# Fri3D_2020_GameOn_01.net
KiCad netlist of a schematic drawn in Altium Designer
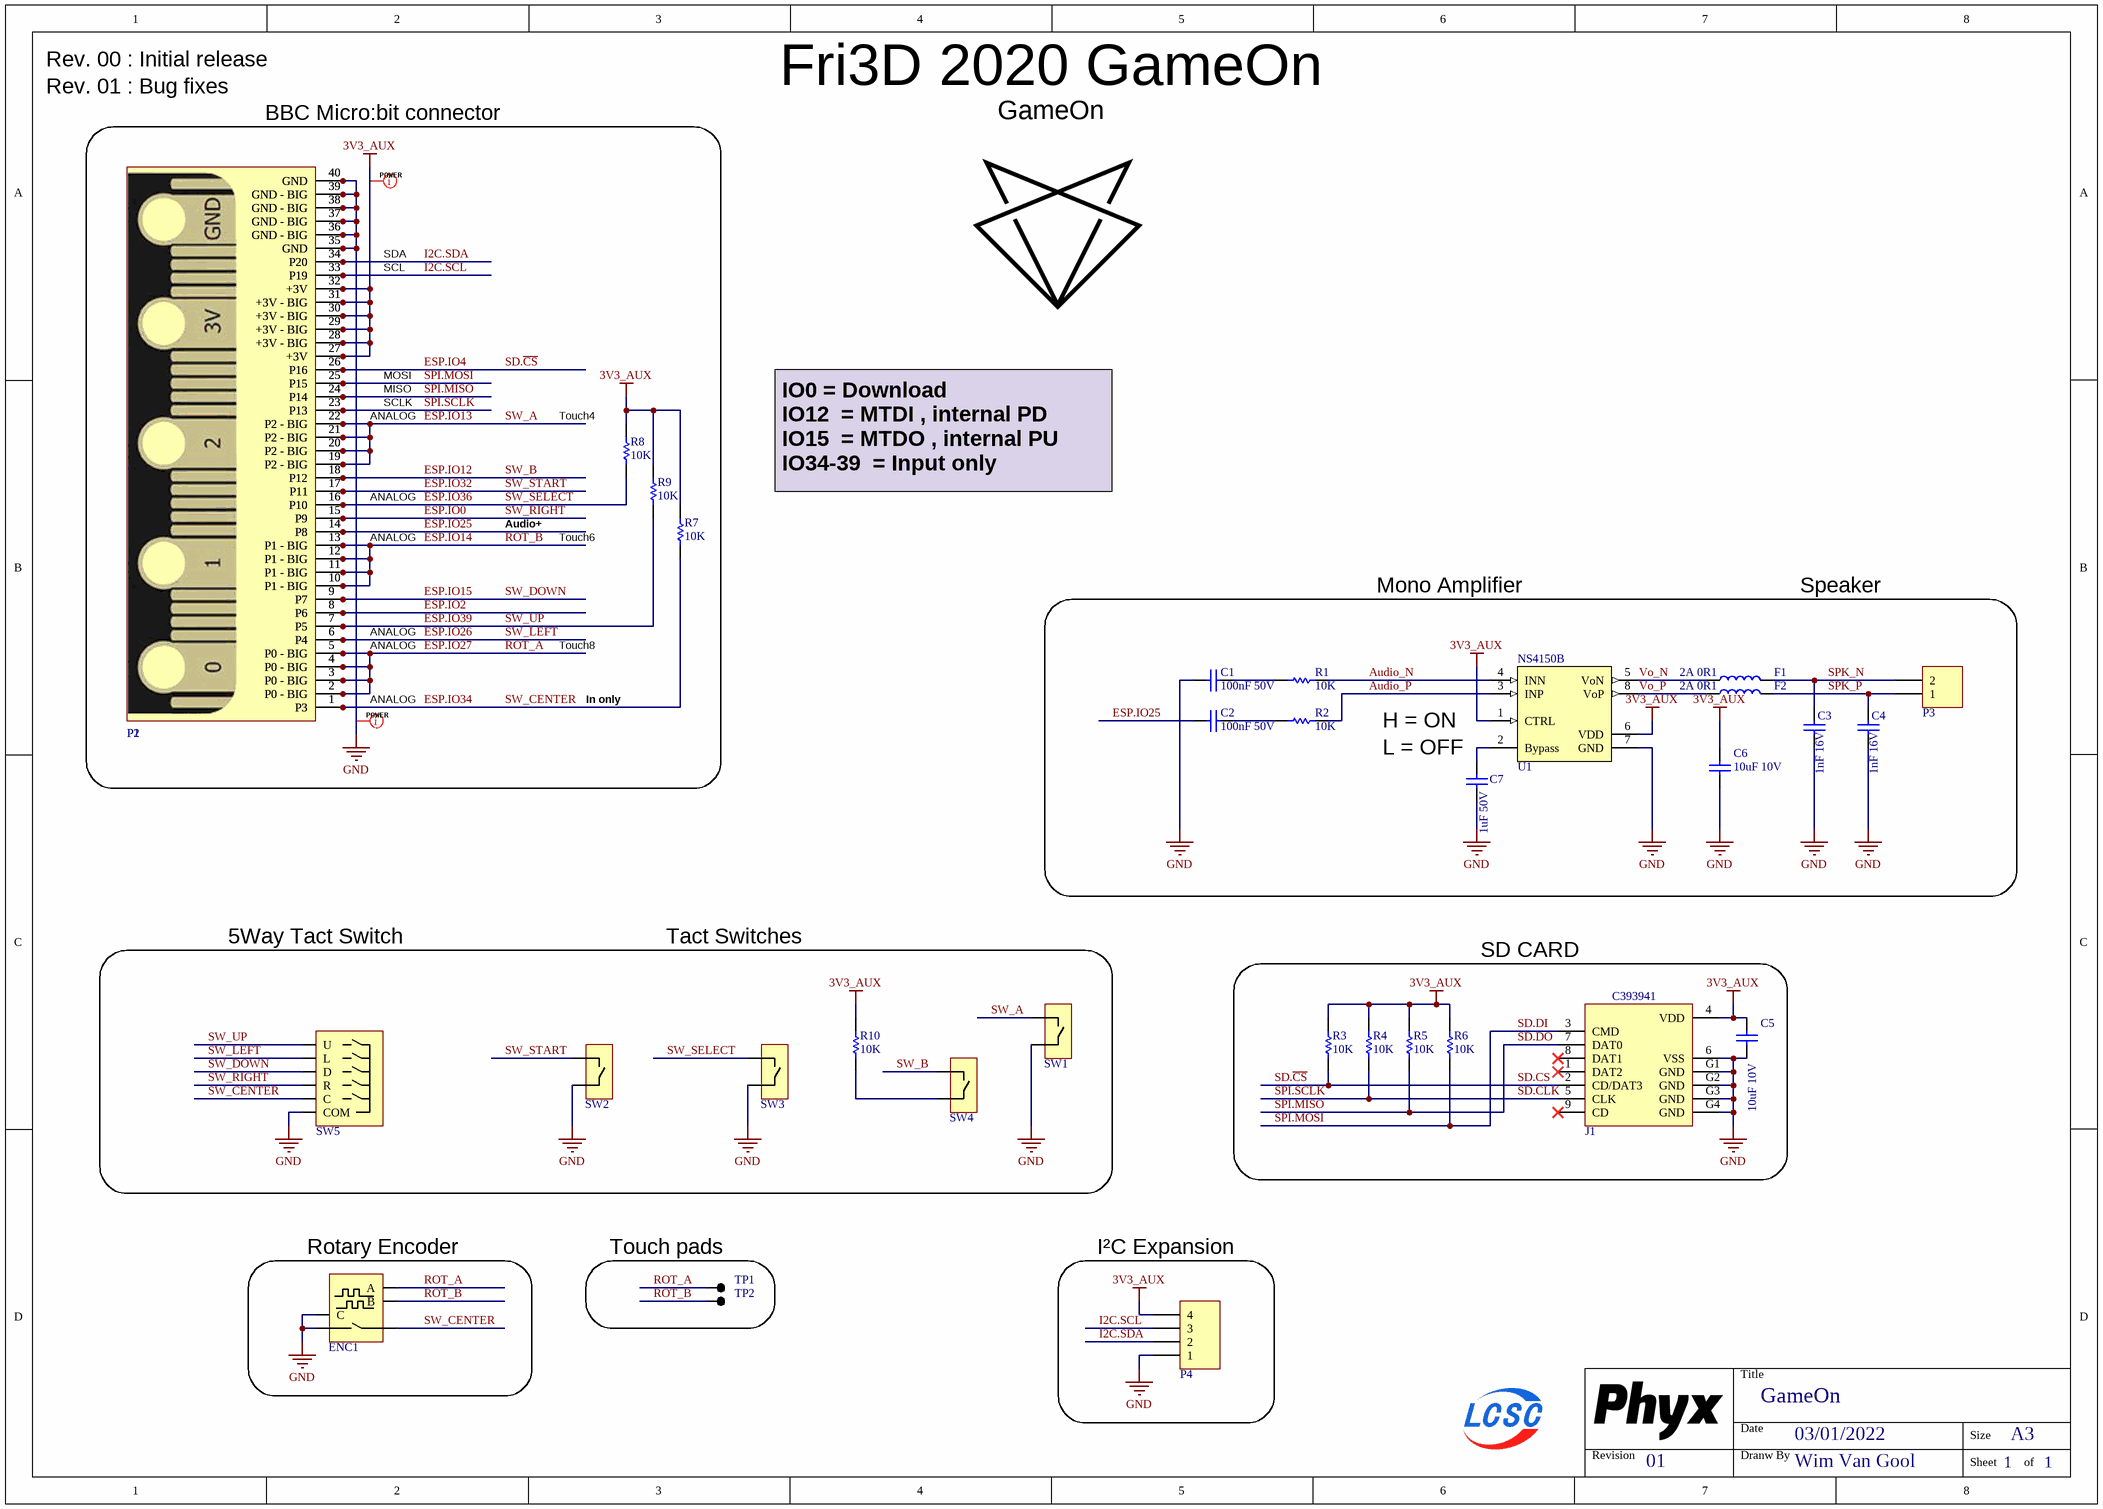
[diagram p0: Fri3D_2020_GameOn_01.SchDoc]

(export (version "E")
  (design (tool "Eeschema 10.0.6"))
  (components
    (comp (ref "C1")
      (value "100nF 50V")
      (footprint "C0603_N")
      (description "Capacitor Ceramic")
      (fields (field (name "Comment") "CAP_CERAMIC"))
      (libsource (lib "Phyx_Components") (part "CAP_CERAMIC"))
    )
    (comp (ref "C2")
      (value "100nF 50V")
      (footprint "C0603_N")
      (description "Capacitor Ceramic")
      (fields (field (name "Comment") "CAP_CERAMIC"))
      (libsource (lib "Phyx_Components") (part "CAP_CERAMIC"))
    )
    (comp (ref "C3")
      (value "1nF 16V")
      (footprint "C0603_N")
      (description "Capacitor Ceramic")
      (fields (field (name "Comment") "CAP_CERAMIC"))
      (libsource (lib "Phyx_Components") (part "CAP_CERAMIC"))
    )
    (comp (ref "C4")
      (value "1nF 16V")
      (footprint "C0603_N")
      (description "Capacitor Ceramic")
      (fields (field (name "Comment") "CAP_CERAMIC"))
      (libsource (lib "Phyx_Components") (part "CAP_CERAMIC"))
    )
    (comp (ref "C5")
      (value "10uF 10V")
      (footprint "C0805_N")
      (description "Capacitor Ceramic")
      (fields (field (name "Comment") "CAP_CERAMIC"))
      (libsource (lib "Phyx_Components") (part "CAP_CERAMIC"))
    )
    (comp (ref "C6")
      (value "10uF 10V")
      (footprint "C0805_N")
      (description "Capacitor Ceramic")
      (fields (field (name "Comment") "CAP_CERAMIC"))
      (libsource (lib "Phyx_Components") (part "CAP_CERAMIC"))
    )
    (comp (ref "C7")
      (value "1uF 50V")
      (footprint "C0603_N")
      (description "Capacitor Ceramic")
      (fields (field (name "Comment") "CAP_CERAMIC"))
      (libsource (lib "Phyx_Components") (part "CAP_CERAMIC"))
    )
    (comp (ref "ENC1")
      (value "Rotary Encoder with Switch")
      (footprint "PEC11-4215F-S0024")
      (libsource (lib "Phyx_Components") (part "ROT_ENC_3P_SW"))
    )
    (comp (ref "F1")
      (value "2A 0R1")
      (footprint "L0805")
      (fields (field (name "Comment") "FERRITE"))
      (libsource (lib "Phyx_Components") (part "FERRITE"))
    )
    (comp (ref "F2")
      (value "2A 0R1")
      (footprint "L0805")
      (fields (field (name "Comment") "FERRITE"))
      (libsource (lib "Phyx_Components") (part "FERRITE"))
    )
    (comp (ref "J1")
      (value "Micro SD PiPo Push-Push")
      (footprint "TFP09-2-12B")
      (description "=Description")
      (fields (field (name "SUPPLIER PART NUMBER 1") "C393941"))
      (libsource (lib "Phyx_Components") (part "TFP09-2-12B"))
    )
    (comp (ref "P1")
      (value "MicroBit 90deg connector Cylconn")
      (footprint "MicroBIT_CYLCONN_SMD_90")
      (libsource (lib "Phyx_Components") (part "Header 40_MicroBit"))
    )
    (comp (ref "P2")
      (value "MicroBit 180deg connector Cylconn")
      (footprint "MicroBIT_CYLCONN_SMD_180")
      (libsource (lib "Phyx_Components") (part "Header 40_MicroBit"))
    )
    (comp (ref "P3")
      (value "Header 2")
      (footprint "HDR1X2")
      (libsource (lib "Phyx_Components") (part "Header 2"))
    )
    (comp (ref "P4")
      (value "Header 4")
      (footprint "HDR1X4")
      (libsource (lib "Phyx_Components") (part "Header 4"))
    )
    (comp (ref "R1")
      (value "10K")
      (footprint "R0603_N")
      (fields (field (name "Comment") "RESISTOR"))
      (libsource (lib "Phyx_Components") (part "RESISTOR"))
    )
    (comp (ref "R2")
      (value "10K")
      (footprint "R0603_N")
      (fields (field (name "Comment") "RESISTOR"))
      (libsource (lib "Phyx_Components") (part "RESISTOR"))
    )
    (comp (ref "R3")
      (value "10K")
      (footprint "R0603_N")
      (fields (field (name "Comment") "RESISTOR"))
      (libsource (lib "Phyx_Components") (part "RESISTOR"))
    )
    (comp (ref "R4")
      (value "10K")
      (footprint "R0603_N")
      (fields (field (name "Comment") "RESISTOR"))
      (libsource (lib "Phyx_Components") (part "RESISTOR"))
    )
    (comp (ref "R5")
      (value "10K")
      (footprint "R0603_N")
      (fields (field (name "Comment") "RESISTOR"))
      (libsource (lib "Phyx_Components") (part "RESISTOR"))
    )
    (comp (ref "R6")
      (value "10K")
      (footprint "R0603_N")
      (fields (field (name "Comment") "RESISTOR"))
      (libsource (lib "Phyx_Components") (part "RESISTOR"))
    )
    (comp (ref "R7")
      (value "10K")
      (footprint "R0603_N")
      (fields (field (name "Comment") "RESISTOR"))
      (libsource (lib "Phyx_Components") (part "RESISTOR"))
    )
    (comp (ref "R8")
      (value "10K")
      (footprint "R0603_N")
      (fields (field (name "Comment") "RESISTOR"))
      (libsource (lib "Phyx_Components") (part "RESISTOR"))
    )
    (comp (ref "R9")
      (value "10K")
      (footprint "R0603_N")
      (fields (field (name "Comment") "RESISTOR"))
      (libsource (lib "Phyx_Components") (part "RESISTOR"))
    )
    (comp (ref "R10")
      (value "10K")
      (footprint "R0603_N")
      (fields (field (name "Comment") "RESISTOR"))
      (libsource (lib "Phyx_Components") (part "RESISTOR"))
    )
    (comp (ref "SW1")
      (value "Default TH TACT")
      (footprint "TACTSW")
      (libsource (lib "Phyx_Components") (part "SW_TACT"))
    )
    (comp (ref "SW2")
      (value "Default TH TACT")
      (footprint "TACTSW")
      (libsource (lib "Phyx_Components") (part "SW_TACT"))
    )
    (comp (ref "SW3")
      (value "Default TH TACT")
      (footprint "TACTSW")
      (libsource (lib "Phyx_Components") (part "SW_TACT"))
    )
    (comp (ref "SW4")
      (value "Default TH TACT")
      (footprint "TACTSW")
      (libsource (lib "Phyx_Components") (part "SW_TACT"))
    )
    (comp (ref "SW5")
      (value "5Way Tact switch")
      (footprint "TACTSW_5W_K1-1506DN-01")
      (libsource (lib "Phyx_Components") (part "SW_TACT_5WAY"))
    )
    (comp (ref "TP1")
      (value "TEST_PAD")
      (footprint "TP_1.2mm")
      (libsource (lib "Phyx_Components") (part "TEST_PAD"))
    )
    (comp (ref "TP2")
      (value "TEST_PAD")
      (footprint "TP_1.2mm")
      (libsource (lib "Phyx_Components") (part "TEST_PAD"))
    )
    (comp (ref "U1")
      (value "NS4150B")
      (footprint "MAX_uSOP8")
      (description "=Description")
      (fields (field (name "Comment") "5W Class D mono amplifier inducter-less Differential input MSOP8"))
      (libsource (lib "Phyx_Components") (part "NS4150"))
    )
  )
  (nets
    (net (code "1") (name "/Audio_N") (class "Default")
      (node (ref "R1") (pin "2") (pinfunction "2_2") (pintype "passive"))
      (node (ref "U1") (pin "4") (pinfunction "INN_4") (pintype "input"))
    )
    (net (code "2") (name "/Audio_P") (class "Default")
      (node (ref "R2") (pin "2") (pinfunction "2_2") (pintype "passive"))
      (node (ref "U1") (pin "3") (pinfunction "INP_3") (pintype "input"))
    )
    (net (code "3") (name "/ESP.IO0") (class "Default")
      (node (ref "P1") (pin "15") (pinfunction "P9_15") (pintype "passive"))
      (node (ref "P2") (pin "15") (pinfunction "P9_15") (pintype "passive"))
      (node (ref "SW5") (pin "5") (pinfunction "R_5") (pintype "passive"))
    )
    (net (code "4") (name "/ESP.IO2") (class "Default")
      (node (ref "P1") (pin "8") (pinfunction "P6_8") (pintype "passive"))
      (node (ref "P2") (pin "8") (pinfunction "P6_8") (pintype "passive"))
    )
    (net (code "5") (name "/ESP.IO4") (class "Default")
      (node (ref "J1") (pin "2") (pinfunction "CD/DAT3_2") (pintype "passive"))
      (node (ref "P1") (pin "26") (pinfunction "P16_26") (pintype "passive"))
      (node (ref "P2") (pin "26") (pinfunction "P16_26") (pintype "passive"))
      (node (ref "R3") (pin "2") (pinfunction "2_2") (pintype "passive"))
    )
    (net (code "6") (name "/ESP.IO12") (class "Default")
      (node (ref "P1") (pin "18") (pinfunction "P12_18") (pintype "passive"))
      (node (ref "P2") (pin "18") (pinfunction "P12_18") (pintype "passive"))
      (node (ref "SW4") (pin "1") (pinfunction "1_1") (pintype "passive"))
    )
    (net (code "7") (name "/ESP.IO13") (class "Default")
      (node (ref "P1") (pin "19") (pinfunction "P2_-_BIG_19") (pintype "passive"))
      (node (ref "P1") (pin "20") (pinfunction "P2_-_BIG_20") (pintype "passive"))
      (node (ref "P1") (pin "21") (pinfunction "P2_-_BIG_21") (pintype "passive"))
      (node (ref "P1") (pin "22") (pinfunction "P2_-_BIG_22") (pintype "passive"))
      (node (ref "P2") (pin "19") (pinfunction "P2_-_BIG_19") (pintype "passive"))
      (node (ref "P2") (pin "20") (pinfunction "P2_-_BIG_20") (pintype "passive"))
      (node (ref "P2") (pin "21") (pinfunction "P2_-_BIG_21") (pintype "passive"))
      (node (ref "P2") (pin "22") (pinfunction "P2_-_BIG_22") (pintype "passive"))
      (node (ref "SW1") (pin "1") (pinfunction "1_1") (pintype "passive"))
    )
    (net (code "8") (name "/ESP.IO14") (class "Default")
      (node (ref "ENC1") (pin "B") (pinfunction "B_B") (pintype "passive"))
      (node (ref "P1") (pin "10") (pinfunction "P1_-_BIG_10") (pintype "passive"))
      (node (ref "P1") (pin "11") (pinfunction "P1_-_BIG_11") (pintype "passive"))
      (node (ref "P1") (pin "12") (pinfunction "P1_-_BIG_12") (pintype "passive"))
      (node (ref "P1") (pin "13") (pinfunction "P1_-_BIG_13") (pintype "passive"))
      (node (ref "P2") (pin "10") (pinfunction "P1_-_BIG_10") (pintype "passive"))
      (node (ref "P2") (pin "11") (pinfunction "P1_-_BIG_11") (pintype "passive"))
      (node (ref "P2") (pin "12") (pinfunction "P1_-_BIG_12") (pintype "passive"))
      (node (ref "P2") (pin "13") (pinfunction "P1_-_BIG_13") (pintype "passive"))
      (node (ref "TP2") (pin "1") (pinfunction "1_1") (pintype "passive"))
    )
    (net (code "9") (name "/ESP.IO15") (class "Default")
      (node (ref "P1") (pin "9") (pinfunction "P7_9") (pintype "passive"))
      (node (ref "P2") (pin "9") (pinfunction "P7_9") (pintype "passive"))
      (node (ref "SW5") (pin "3") (pinfunction "D_3") (pintype "passive"))
    )
    (net (code "10") (name "/ESP.IO25") (class "Default")
      (node (ref "C2") (pin "2") (pinfunction "2_2") (pintype "passive"))
      (node (ref "P1") (pin "14") (pinfunction "P8_14") (pintype "passive"))
      (node (ref "P2") (pin "14") (pinfunction "P8_14") (pintype "passive"))
    )
    (net (code "11") (name "/ESP.IO26") (class "Default")
      (node (ref "P1") (pin "6") (pinfunction "P4_6") (pintype "passive"))
      (node (ref "P2") (pin "6") (pinfunction "P4_6") (pintype "passive"))
      (node (ref "SW5") (pin "2") (pinfunction "L_2") (pintype "passive"))
    )
    (net (code "12") (name "/ESP.IO27") (class "Default")
      (node (ref "ENC1") (pin "A") (pinfunction "A_A") (pintype "passive"))
      (node (ref "P1") (pin "2") (pinfunction "P0_-_BIG_2") (pintype "passive"))
      (node (ref "P1") (pin "3") (pinfunction "P0_-_BIG_3") (pintype "passive"))
      (node (ref "P1") (pin "4") (pinfunction "P0_-_BIG_4") (pintype "passive"))
      (node (ref "P1") (pin "5") (pinfunction "P0_-_BIG_5") (pintype "passive"))
      (node (ref "P2") (pin "2") (pinfunction "P0_-_BIG_2") (pintype "passive"))
      (node (ref "P2") (pin "3") (pinfunction "P0_-_BIG_3") (pintype "passive"))
      (node (ref "P2") (pin "4") (pinfunction "P0_-_BIG_4") (pintype "passive"))
      (node (ref "P2") (pin "5") (pinfunction "P0_-_BIG_5") (pintype "passive"))
      (node (ref "TP1") (pin "1") (pinfunction "1_1") (pintype "passive"))
    )
    (net (code "13") (name "/ESP.IO32") (class "Default")
      (node (ref "P1") (pin "17") (pinfunction "P11_17") (pintype "passive"))
      (node (ref "P2") (pin "17") (pinfunction "P11_17") (pintype "passive"))
      (node (ref "SW2") (pin "1") (pinfunction "1_1") (pintype "passive"))
    )
    (net (code "14") (name "/ESP.IO34") (class "Default")
      (node (ref "ENC1") (pin "2") (pinfunction "2_2") (pintype "passive"))
      (node (ref "P1") (pin "1") (pinfunction "P3_1") (pintype "passive"))
      (node (ref "P2") (pin "1") (pinfunction "P3_1") (pintype "passive"))
      (node (ref "R7") (pin "2") (pinfunction "2_2") (pintype "passive"))
      (node (ref "SW5") (pin "6") (pinfunction "C_6") (pintype "passive"))
    )
    (net (code "15") (name "/ESP.IO36") (class "Default")
      (node (ref "P1") (pin "16") (pinfunction "P10_16") (pintype "passive"))
      (node (ref "P2") (pin "16") (pinfunction "P10_16") (pintype "passive"))
      (node (ref "R8") (pin "2") (pinfunction "2_2") (pintype "passive"))
      (node (ref "SW3") (pin "1") (pinfunction "1_1") (pintype "passive"))
    )
    (net (code "16") (name "/ESP.IO39") (class "Default")
      (node (ref "P1") (pin "7") (pinfunction "P5_7") (pintype "passive"))
      (node (ref "P2") (pin "7") (pinfunction "P5_7") (pintype "passive"))
      (node (ref "R9") (pin "2") (pinfunction "2_2") (pintype "passive"))
      (node (ref "SW5") (pin "1") (pinfunction "U_1") (pintype "passive"))
    )
    (net (code "17") (name "/I2C.SCL") (class "Default")
      (node (ref "P1") (pin "33") (pinfunction "P19_33") (pintype "passive"))
      (node (ref "P2") (pin "33") (pinfunction "P19_33") (pintype "passive"))
      (node (ref "P4") (pin "3") (pinfunction "3_3") (pintype "passive"))
    )
    (net (code "18") (name "/I2C.SDA") (class "Default")
      (node (ref "P1") (pin "34") (pinfunction "P20_34") (pintype "passive"))
      (node (ref "P2") (pin "34") (pinfunction "P20_34") (pintype "passive"))
      (node (ref "P4") (pin "2") (pinfunction "2_2") (pintype "passive"))
    )
    (net (code "19") (name "/SD.CLK") (class "Default")
      (node (ref "J1") (pin "5") (pinfunction "CLK_5") (pintype "passive"))
      (node (ref "P1") (pin "23") (pinfunction "P13_23") (pintype "passive"))
      (node (ref "P2") (pin "23") (pinfunction "P13_23") (pintype "passive"))
      (node (ref "R4") (pin "2") (pinfunction "2_2") (pintype "passive"))
    )
    (net (code "20") (name "/SD.DI") (class "Default")
      (node (ref "J1") (pin "3") (pinfunction "CMD_3") (pintype "passive"))
      (node (ref "P1") (pin "25") (pinfunction "P15_25") (pintype "passive"))
      (node (ref "P2") (pin "25") (pinfunction "P15_25") (pintype "passive"))
      (node (ref "R6") (pin "2") (pinfunction "2_2") (pintype "passive"))
    )
    (net (code "21") (name "/SD.DO") (class "Default")
      (node (ref "J1") (pin "7") (pinfunction "DAT0_7") (pintype "passive"))
      (node (ref "P1") (pin "24") (pinfunction "P14_24") (pintype "passive"))
      (node (ref "P2") (pin "24") (pinfunction "P14_24") (pintype "passive"))
      (node (ref "R5") (pin "2") (pinfunction "2_2") (pintype "passive"))
    )
    (net (code "22") (name "/SPK_N") (class "Default")
      (node (ref "C3") (pin "1") (pinfunction "1_1") (pintype "passive"))
      (node (ref "F1") (pin "2") (pinfunction "2_2") (pintype "passive"))
      (node (ref "P3") (pin "2") (pinfunction "2_2") (pintype "passive"))
    )
    (net (code "23") (name "/SPK_P") (class "Default")
      (node (ref "C4") (pin "1") (pinfunction "1_1") (pintype "passive"))
      (node (ref "F2") (pin "2") (pinfunction "2_2") (pintype "passive"))
      (node (ref "P3") (pin "1") (pinfunction "1_1") (pintype "passive"))
    )
    (net (code "24") (name "/Vo_N") (class "Default")
      (node (ref "F1") (pin "1") (pinfunction "1_1") (pintype "passive"))
      (node (ref "U1") (pin "5") (pinfunction "VoN_5") (pintype "output"))
    )
    (net (code "25") (name "/Vo_P") (class "Default")
      (node (ref "F2") (pin "1") (pinfunction "1_1") (pintype "passive"))
      (node (ref "U1") (pin "8") (pinfunction "VoP_8") (pintype "output"))
    )
    (net (code "26") (name "3V3_AUX") (class "Default")
      (node (ref "C5") (pin "1") (pinfunction "1_1") (pintype "passive"))
      (node (ref "C6") (pin "1") (pinfunction "1_1") (pintype "passive"))
      (node (ref "J1") (pin "4") (pinfunction "VDD_4") (pintype "power_in"))
      (node (ref "P1") (pin "27") (pinfunction "+3V_27") (pintype "passive"))
      (node (ref "P1") (pin "28") (pinfunction "+3V_-_BIG_28") (pintype "passive"))
      (node (ref "P1") (pin "29") (pinfunction "+3V_-_BIG_29") (pintype "passive"))
      (node (ref "P1") (pin "30") (pinfunction "+3V_-_BIG_30") (pintype "passive"))
      (node (ref "P1") (pin "31") (pinfunction "+3V_-_BIG_31") (pintype "passive"))
      (node (ref "P1") (pin "32") (pinfunction "+3V_32") (pintype "passive"))
      (node (ref "P2") (pin "27") (pinfunction "+3V_27") (pintype "passive"))
      (node (ref "P2") (pin "28") (pinfunction "+3V_-_BIG_28") (pintype "passive"))
      (node (ref "P2") (pin "29") (pinfunction "+3V_-_BIG_29") (pintype "passive"))
      (node (ref "P2") (pin "30") (pinfunction "+3V_-_BIG_30") (pintype "passive"))
      (node (ref "P2") (pin "31") (pinfunction "+3V_-_BIG_31") (pintype "passive"))
      (node (ref "P2") (pin "32") (pinfunction "+3V_32") (pintype "passive"))
      (node (ref "P4") (pin "4") (pinfunction "4_4") (pintype "passive"))
      (node (ref "R10") (pin "1") (pinfunction "1_1") (pintype "passive"))
      (node (ref "R3") (pin "1") (pinfunction "1_1") (pintype "passive"))
      (node (ref "R4") (pin "1") (pinfunction "1_1") (pintype "passive"))
      (node (ref "R5") (pin "1") (pinfunction "1_1") (pintype "passive"))
      (node (ref "R6") (pin "1") (pinfunction "1_1") (pintype "passive"))
      (node (ref "R7") (pin "1") (pinfunction "1_1") (pintype "passive"))
      (node (ref "R8") (pin "1") (pinfunction "1_1") (pintype "passive"))
      (node (ref "R9") (pin "1") (pinfunction "1_1") (pintype "passive"))
      (node (ref "U1") (pin "1") (pinfunction "CTRL_1") (pintype "input"))
      (node (ref "U1") (pin "6") (pinfunction "VDD_6") (pintype "power_in"))
    )
    (net (code "27") (name "GND") (class "Default")
      (node (ref "C1") (pin "2") (pinfunction "2_2") (pintype "passive"))
      (node (ref "C3") (pin "2") (pinfunction "2_2") (pintype "passive"))
      (node (ref "C4") (pin "2") (pinfunction "2_2") (pintype "passive"))
      (node (ref "C5") (pin "2") (pinfunction "2_2") (pintype "passive"))
      (node (ref "C6") (pin "2") (pinfunction "2_2") (pintype "passive"))
      (node (ref "C7") (pin "2") (pinfunction "2_2") (pintype "passive"))
      (node (ref "ENC1") (pin "1") (pinfunction "1_1") (pintype "passive"))
      (node (ref "ENC1") (pin "C") (pinfunction "C_C") (pintype "passive"))
      (node (ref "J1") (pin "6") (pinfunction "VSS_6") (pintype "power_in"))
      (node (ref "J1") (pin "G1") (pinfunction "GND_G1") (pintype "power_in"))
      (node (ref "J1") (pin "G2") (pinfunction "GND_G2") (pintype "power_in"))
      (node (ref "J1") (pin "G3") (pinfunction "GND_G3") (pintype "power_in"))
      (node (ref "J1") (pin "G4") (pinfunction "GND_G4") (pintype "power_in"))
      (node (ref "P1") (pin "35") (pinfunction "GND_35") (pintype "passive"))
      (node (ref "P1") (pin "36") (pinfunction "GND_-_BIG_36") (pintype "passive"))
      (node (ref "P1") (pin "37") (pinfunction "GND_-_BIG_37") (pintype "passive"))
      (node (ref "P1") (pin "38") (pinfunction "GND_-_BIG_38") (pintype "passive"))
      (node (ref "P1") (pin "39") (pinfunction "GND_-_BIG_39") (pintype "passive"))
      (node (ref "P1") (pin "40") (pinfunction "GND_40") (pintype "passive"))
      (node (ref "P2") (pin "35") (pinfunction "GND_35") (pintype "passive"))
      (node (ref "P2") (pin "36") (pinfunction "GND_-_BIG_36") (pintype "passive"))
      (node (ref "P2") (pin "37") (pinfunction "GND_-_BIG_37") (pintype "passive"))
      (node (ref "P2") (pin "38") (pinfunction "GND_-_BIG_38") (pintype "passive"))
      (node (ref "P2") (pin "39") (pinfunction "GND_-_BIG_39") (pintype "passive"))
      (node (ref "P2") (pin "40") (pinfunction "GND_40") (pintype "passive"))
      (node (ref "P4") (pin "1") (pinfunction "1_1") (pintype "passive"))
      (node (ref "SW1") (pin "2") (pinfunction "2_2") (pintype "passive"))
      (node (ref "SW2") (pin "2") (pinfunction "2_2") (pintype "passive"))
      (node (ref "SW3") (pin "2") (pinfunction "2_2") (pintype "passive"))
      (node (ref "SW5") (pin "4") (pinfunction "COM_4") (pintype "passive"))
      (node (ref "U1") (pin "7") (pinfunction "GND_7") (pintype "power_in"))
    )
    (net (code "28") (name "Net-(C1-Pad1)") (class "Default")
      (node (ref "C1") (pin "1") (pinfunction "1_1") (pintype "passive"))
      (node (ref "R1") (pin "1") (pinfunction "1_1") (pintype "passive"))
    )
    (net (code "29") (name "Net-(C2-Pad1)") (class "Default")
      (node (ref "C2") (pin "1") (pinfunction "1_1") (pintype "passive"))
      (node (ref "R2") (pin "1") (pinfunction "1_1") (pintype "passive"))
    )
    (net (code "30") (name "Net-(R10-Pad2)") (class "Default")
      (node (ref "R10") (pin "2") (pinfunction "2_2") (pintype "passive"))
      (node (ref "SW4") (pin "2") (pinfunction "2_2") (pintype "passive"))
    )
    (net (code "31") (name "Net-(U1-Bypass)") (class "Default")
      (node (ref "C7") (pin "1") (pinfunction "1_1") (pintype "passive"))
      (node (ref "U1") (pin "2") (pinfunction "Bypass_2") (pintype "passive"))
    )
    (net (code "32") (name "unconnected-(J1-CD-Pad9)") (class "Default")
      (node (ref "J1") (pin "9") (pinfunction "CD_9") (pintype "passive+no_connect"))
    )
    (net (code "33") (name "unconnected-(J1-DAT1-Pad8)") (class "Default")
      (node (ref "J1") (pin "8") (pinfunction "DAT1_8") (pintype "passive+no_connect"))
    )
    (net (code "34") (name "unconnected-(J1-DAT2-Pad1)") (class "Default")
      (node (ref "J1") (pin "1") (pinfunction "DAT2_1") (pintype "passive+no_connect"))
    )
  )
)
